# Handdisplay2.net
KiCad netlist of a schematic drawn in EAGLE
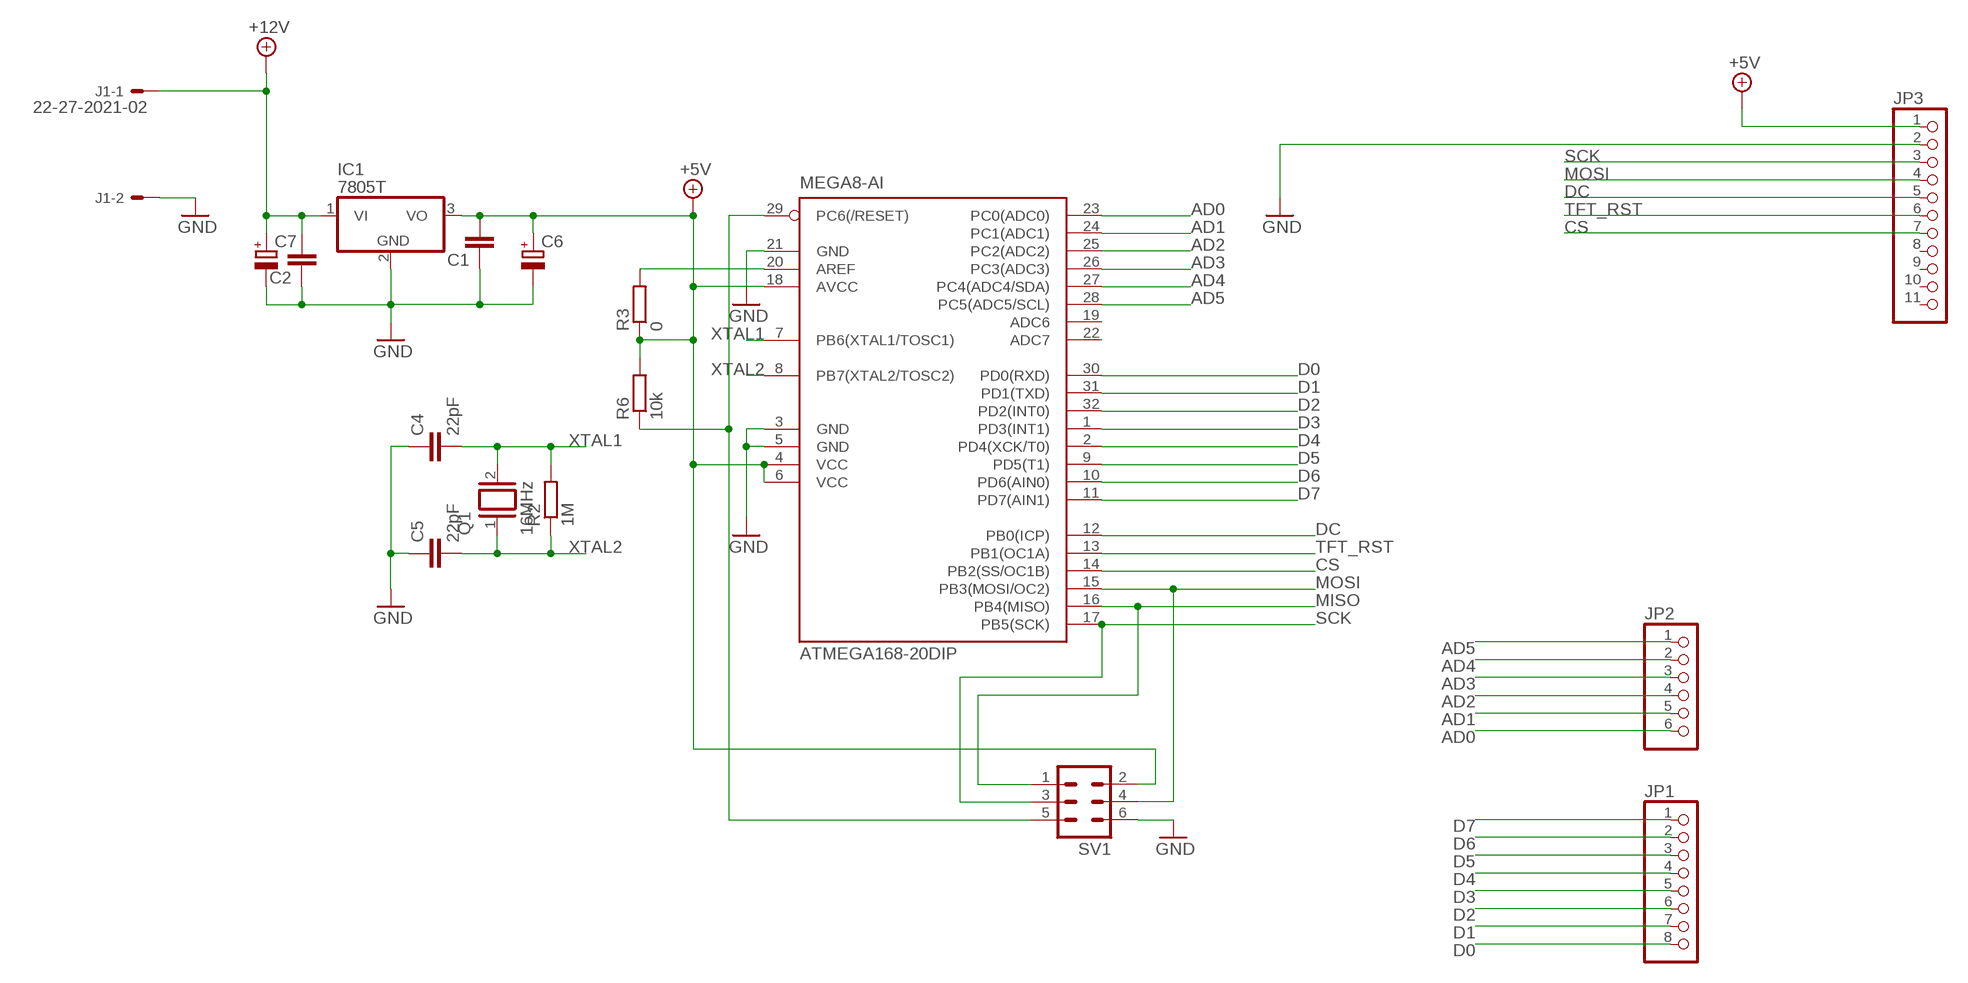
[diagram p0: schematic, sheet 1]

(export (version "E")
  (design (tool "Eeschema 10.0.6"))
  (components
    (comp (ref "ATMEGA168-20DIP")
      (value "MEGA8-AI")
      (footprint "eagle-import:TQFP32-08")
      (fields (field (name "MPN") "ATMEGA8-16AU"))
      (libsource (lib "eagle-import") (part "MEGA8-AI"))
    )
    (comp (ref "C1")
      (value "C-EUC0805")
      (footprint "eagle-import:C0805")
      (libsource (lib "eagle-import") (part "C-EUC0805"))
    )
    (comp (ref "C2")
      (value "C-EUC0805")
      (footprint "eagle-import:C0805")
      (libsource (lib "eagle-import") (part "C-EUC0805"))
    )
    (comp (ref "C4")
      (value "22pF")
      (footprint "eagle-import:C0805")
      (libsource (lib "eagle-import") (part "C-EUC0805"))
    )
    (comp (ref "C5")
      (value "22pF")
      (footprint "eagle-import:C0805")
      (libsource (lib "eagle-import") (part "C-EUC0805"))
    )
    (comp (ref "C6")
      (value "CPOL-EUUD-5X5,8")
      (footprint "eagle-import:UD-5X5,8_NICHICON")
      (libsource (lib "eagle-import") (part "CPOL-EUUD-5X5,8"))
    )
    (comp (ref "C7")
      (value "CPOL-EUUD-5X5,8")
      (footprint "eagle-import:UD-5X5,8_NICHICON")
      (libsource (lib "eagle-import") (part "CPOL-EUUD-5X5,8"))
    )
    (comp (ref "IC1")
      (value "7805T")
      (footprint "eagle-import:TO220H")
      (libsource (lib "eagle-import") (part "78T05"))
    )
    (comp (ref "J1")
      (value "22-27-2021-02")
      (footprint "eagle-import:6410-02")
      (libsource (lib "eagle-import") (part "22-?-0227-2021"))
    )
    (comp (ref "JP1")
      (value "PINHD-1X8")
      (footprint "eagle-import:1X08")
      (libsource (lib "eagle-import") (part "PINHD-1X8"))
    )
    (comp (ref "JP2")
      (value "PINHD-1X6")
      (footprint "eagle-import:1X06")
      (libsource (lib "eagle-import") (part "PINHD-1X6"))
    )
    (comp (ref "JP3")
      (value "PINHD-1X11")
      (footprint "eagle-import:1X11")
      (libsource (lib "eagle-import") (part "PINHD-1X11"))
    )
    (comp (ref "Q1")
      (value "16MHz")
      (footprint "eagle-import:QS")
      (libsource (lib "eagle-import") (part "XTAL/S"))
    )
    (comp (ref "R2")
      (value "1M")
      (footprint "eagle-import:R0805")
      (libsource (lib "eagle-import") (part "R-EU_R0805"))
    )
    (comp (ref "R3")
      (value "0")
      (footprint "eagle-import:R0805")
      (libsource (lib "eagle-import") (part "R-EU_R0805"))
    )
    (comp (ref "R6")
      (value "10k")
      (footprint "eagle-import:R0805")
      (libsource (lib "eagle-import") (part "R-EU_R0805"))
    )
    (comp (ref "SV1")
      (value "ML6")
      (footprint "eagle-import:ML6")
      (libsource (lib "eagle-import") (part "ML6"))
    )
  )
  (nets
    (net (code "1") (name "+5V") (class "Default")
      (node (ref "ATMEGA168-20DIP") (pin "18") (pinfunction "AVCC_18") (pintype "power_in"))
      (node (ref "ATMEGA168-20DIP") (pin "4") (pinfunction "VCC_4") (pintype "power_in"))
      (node (ref "ATMEGA168-20DIP") (pin "6") (pinfunction "VCC_6") (pintype "power_in"))
      (node (ref "C1") (pin "2") (pinfunction "2_2") (pintype "passive"))
      (node (ref "C6") (pin "+") (pinfunction "+_+") (pintype "passive"))
      (node (ref "IC1") (pin "3") (pinfunction "VO_3") (pintype "passive"))
      (node (ref "JP3") (pin "1") (pinfunction "1_1") (pintype "passive"))
      (node (ref "R3") (pin "1") (pinfunction "1_1") (pintype "passive"))
      (node (ref "R6") (pin "2") (pinfunction "2_2") (pintype "passive"))
      (node (ref "SV1") (pin "2") (pinfunction "2_2") (pintype "passive"))
    )
    (net (code "2") (name "+12V") (class "Default")
      (node (ref "C2") (pin "2") (pinfunction "2_2") (pintype "passive"))
      (node (ref "C7") (pin "+") (pinfunction "+_+") (pintype "passive"))
      (node (ref "IC1") (pin "1") (pinfunction "VI_1") (pintype "input"))
      (node (ref "J1") (pin "1") (pinfunction "S_1") (pintype "passive"))
    )
    (net (code "3") (name "/AD0") (class "Default")
      (node (ref "ATMEGA168-20DIP") (pin "23") (pinfunction "PC0(ADC0)_23") (pintype "bidirectional"))
      (node (ref "JP2") (pin "6") (pinfunction "6_6") (pintype "passive"))
    )
    (net (code "4") (name "/AD1") (class "Default")
      (node (ref "ATMEGA168-20DIP") (pin "24") (pinfunction "PC1(ADC1)_24") (pintype "bidirectional"))
      (node (ref "JP2") (pin "5") (pinfunction "5_5") (pintype "passive"))
    )
    (net (code "5") (name "/AD2") (class "Default")
      (node (ref "ATMEGA168-20DIP") (pin "25") (pinfunction "PC2(ADC2)_25") (pintype "bidirectional"))
      (node (ref "JP2") (pin "4") (pinfunction "4_4") (pintype "passive"))
    )
    (net (code "6") (name "/AD3") (class "Default")
      (node (ref "ATMEGA168-20DIP") (pin "26") (pinfunction "PC3(ADC3)_26") (pintype "bidirectional"))
      (node (ref "JP2") (pin "3") (pinfunction "3_3") (pintype "passive"))
    )
    (net (code "7") (name "/AD4") (class "Default")
      (node (ref "ATMEGA168-20DIP") (pin "27") (pinfunction "PC4(ADC4/SDA)_27") (pintype "bidirectional"))
      (node (ref "JP2") (pin "2") (pinfunction "2_2") (pintype "passive"))
    )
    (net (code "8") (name "/AD5") (class "Default")
      (node (ref "ATMEGA168-20DIP") (pin "28") (pinfunction "PC5(ADC5/SCL)_28") (pintype "bidirectional"))
      (node (ref "JP2") (pin "1") (pinfunction "1_1") (pintype "passive"))
    )
    (net (code "9") (name "/CS") (class "Default")
      (node (ref "ATMEGA168-20DIP") (pin "14") (pinfunction "PB2(SS/OC1B)_14") (pintype "bidirectional"))
      (node (ref "JP3") (pin "7") (pinfunction "7_7") (pintype "passive"))
    )
    (net (code "10") (name "/D0") (class "Default")
      (node (ref "ATMEGA168-20DIP") (pin "30") (pinfunction "PD0(RXD)_30") (pintype "bidirectional"))
      (node (ref "JP1") (pin "8") (pinfunction "8_8") (pintype "passive"))
    )
    (net (code "11") (name "/D1") (class "Default")
      (node (ref "ATMEGA168-20DIP") (pin "31") (pinfunction "PD1(TXD)_31") (pintype "bidirectional"))
      (node (ref "JP1") (pin "7") (pinfunction "7_7") (pintype "passive"))
    )
    (net (code "12") (name "/D2") (class "Default")
      (node (ref "ATMEGA168-20DIP") (pin "32") (pinfunction "PD2(INT0)_32") (pintype "bidirectional"))
      (node (ref "JP1") (pin "6") (pinfunction "6_6") (pintype "passive"))
    )
    (net (code "13") (name "/D3") (class "Default")
      (node (ref "ATMEGA168-20DIP") (pin "1") (pinfunction "PD3(INT1)_1") (pintype "bidirectional"))
      (node (ref "JP1") (pin "5") (pinfunction "5_5") (pintype "passive"))
    )
    (net (code "14") (name "/D4") (class "Default")
      (node (ref "ATMEGA168-20DIP") (pin "2") (pinfunction "PD4(XCK/T0)_2") (pintype "bidirectional"))
      (node (ref "JP1") (pin "4") (pinfunction "4_4") (pintype "passive"))
    )
    (net (code "15") (name "/D5") (class "Default")
      (node (ref "ATMEGA168-20DIP") (pin "9") (pinfunction "PD5(T1)_9") (pintype "bidirectional"))
      (node (ref "JP1") (pin "3") (pinfunction "3_3") (pintype "passive"))
    )
    (net (code "16") (name "/D6") (class "Default")
      (node (ref "ATMEGA168-20DIP") (pin "10") (pinfunction "PD6(AIN0)_10") (pintype "bidirectional"))
      (node (ref "JP1") (pin "2") (pinfunction "2_2") (pintype "passive"))
    )
    (net (code "17") (name "/D7") (class "Default")
      (node (ref "ATMEGA168-20DIP") (pin "11") (pinfunction "PD7(AIN1)_11") (pintype "bidirectional"))
      (node (ref "JP1") (pin "1") (pinfunction "1_1") (pintype "passive"))
    )
    (net (code "18") (name "/DC") (class "Default")
      (node (ref "ATMEGA168-20DIP") (pin "12") (pinfunction "PB0(ICP)_12") (pintype "bidirectional"))
      (node (ref "JP3") (pin "5") (pinfunction "5_5") (pintype "passive"))
    )
    (net (code "19") (name "/MISO") (class "Default")
      (node (ref "ATMEGA168-20DIP") (pin "16") (pinfunction "PB4(MISO)_16") (pintype "bidirectional"))
      (node (ref "SV1") (pin "1") (pinfunction "1_1") (pintype "passive"))
    )
    (net (code "20") (name "/MOSI") (class "Default")
      (node (ref "ATMEGA168-20DIP") (pin "15") (pinfunction "PB3(MOSI/OC2)_15") (pintype "bidirectional"))
      (node (ref "JP3") (pin "4") (pinfunction "4_4") (pintype "passive"))
      (node (ref "SV1") (pin "4") (pinfunction "4_4") (pintype "passive"))
    )
    (net (code "21") (name "/SCK") (class "Default")
      (node (ref "ATMEGA168-20DIP") (pin "17") (pinfunction "PB5(SCK)_17") (pintype "bidirectional"))
      (node (ref "JP3") (pin "3") (pinfunction "3_3") (pintype "passive"))
      (node (ref "SV1") (pin "3") (pinfunction "3_3") (pintype "passive"))
    )
    (net (code "22") (name "/TFT_RST") (class "Default")
      (node (ref "ATMEGA168-20DIP") (pin "13") (pinfunction "PB1(OC1A)_13") (pintype "bidirectional"))
      (node (ref "JP3") (pin "6") (pinfunction "6_6") (pintype "passive"))
    )
    (net (code "23") (name "/XTAL1") (class "Default")
      (node (ref "ATMEGA168-20DIP") (pin "7") (pinfunction "PB6(XTAL1/TOSC1)_7") (pintype "bidirectional"))
      (node (ref "C4") (pin "2") (pinfunction "2_2") (pintype "passive"))
      (node (ref "Q1") (pin "2") (pinfunction "2_2") (pintype "passive"))
      (node (ref "R2") (pin "2") (pinfunction "2_2") (pintype "passive"))
    )
    (net (code "24") (name "/XTAL2") (class "Default")
      (node (ref "ATMEGA168-20DIP") (pin "8") (pinfunction "PB7(XTAL2/TOSC2)_8") (pintype "bidirectional"))
      (node (ref "C5") (pin "2") (pinfunction "2_2") (pintype "passive"))
      (node (ref "Q1") (pin "1") (pinfunction "1_1") (pintype "passive"))
      (node (ref "R2") (pin "1") (pinfunction "1_1") (pintype "passive"))
    )
    (net (code "25") (name "GND") (class "Default")
      (node (ref "ATMEGA168-20DIP") (pin "21") (pinfunction "GND_21") (pintype "power_in"))
      (node (ref "ATMEGA168-20DIP") (pin "3") (pinfunction "GND_3") (pintype "power_in"))
      (node (ref "ATMEGA168-20DIP") (pin "5") (pinfunction "GND_5") (pintype "power_in"))
      (node (ref "C1") (pin "1") (pinfunction "1_1") (pintype "passive"))
      (node (ref "C2") (pin "1") (pinfunction "1_1") (pintype "passive"))
      (node (ref "C4") (pin "1") (pinfunction "1_1") (pintype "passive"))
      (node (ref "C5") (pin "1") (pinfunction "1_1") (pintype "passive"))
      (node (ref "C6") (pin "-") (pinfunction "-_-") (pintype "passive"))
      (node (ref "C7") (pin "-") (pinfunction "-_-") (pintype "passive"))
      (node (ref "IC1") (pin "2") (pinfunction "GND_2") (pintype "passive"))
      (node (ref "J1") (pin "2") (pinfunction "S_2") (pintype "passive"))
      (node (ref "JP3") (pin "2") (pinfunction "2_2") (pintype "passive"))
      (node (ref "SV1") (pin "6") (pinfunction "6_6") (pintype "passive"))
    )
    (net (code "26") (name "Net-(ATMEGA168-20DIP-AREF)") (class "Default")
      (node (ref "ATMEGA168-20DIP") (pin "20") (pinfunction "AREF_20") (pintype "passive"))
      (node (ref "R3") (pin "2") (pinfunction "2_2") (pintype "passive"))
    )
    (net (code "27") (name "Net-(ATMEGA168-20DIP-PC6({slash}RESET))") (class "Default")
      (node (ref "ATMEGA168-20DIP") (pin "29") (pinfunction "PC6(/RESET)_29") (pintype "bidirectional"))
      (node (ref "R6") (pin "1") (pinfunction "1_1") (pintype "passive"))
      (node (ref "SV1") (pin "5") (pinfunction "5_5") (pintype "passive"))
    )
    (net (code "28") (name "unconnected-(ATMEGA168-20DIP-ADC6-Pad19)") (class "Default")
      (node (ref "ATMEGA168-20DIP") (pin "19") (pinfunction "ADC6_19") (pintype "bidirectional"))
    )
    (net (code "29") (name "unconnected-(ATMEGA168-20DIP-ADC7-Pad22)") (class "Default")
      (node (ref "ATMEGA168-20DIP") (pin "22") (pinfunction "ADC7_22") (pintype "bidirectional"))
    )
    (net (code "30") (name "unconnected-(JP3-Pad8)") (class "Default")
      (node (ref "JP3") (pin "8") (pinfunction "8_8") (pintype "passive"))
    )
    (net (code "31") (name "unconnected-(JP3-Pad9)") (class "Default")
      (node (ref "JP3") (pin "9") (pinfunction "9_9") (pintype "passive"))
    )
    (net (code "32") (name "unconnected-(JP3-Pad10)") (class "Default")
      (node (ref "JP3") (pin "10") (pinfunction "10_10") (pintype "passive"))
    )
    (net (code "33") (name "unconnected-(JP3-Pad11)") (class "Default")
      (node (ref "JP3") (pin "11") (pinfunction "11_11") (pintype "passive"))
    )
  )
)
